# Sheet1.net
KiCad netlist of a schematic drawn in Altium Designer
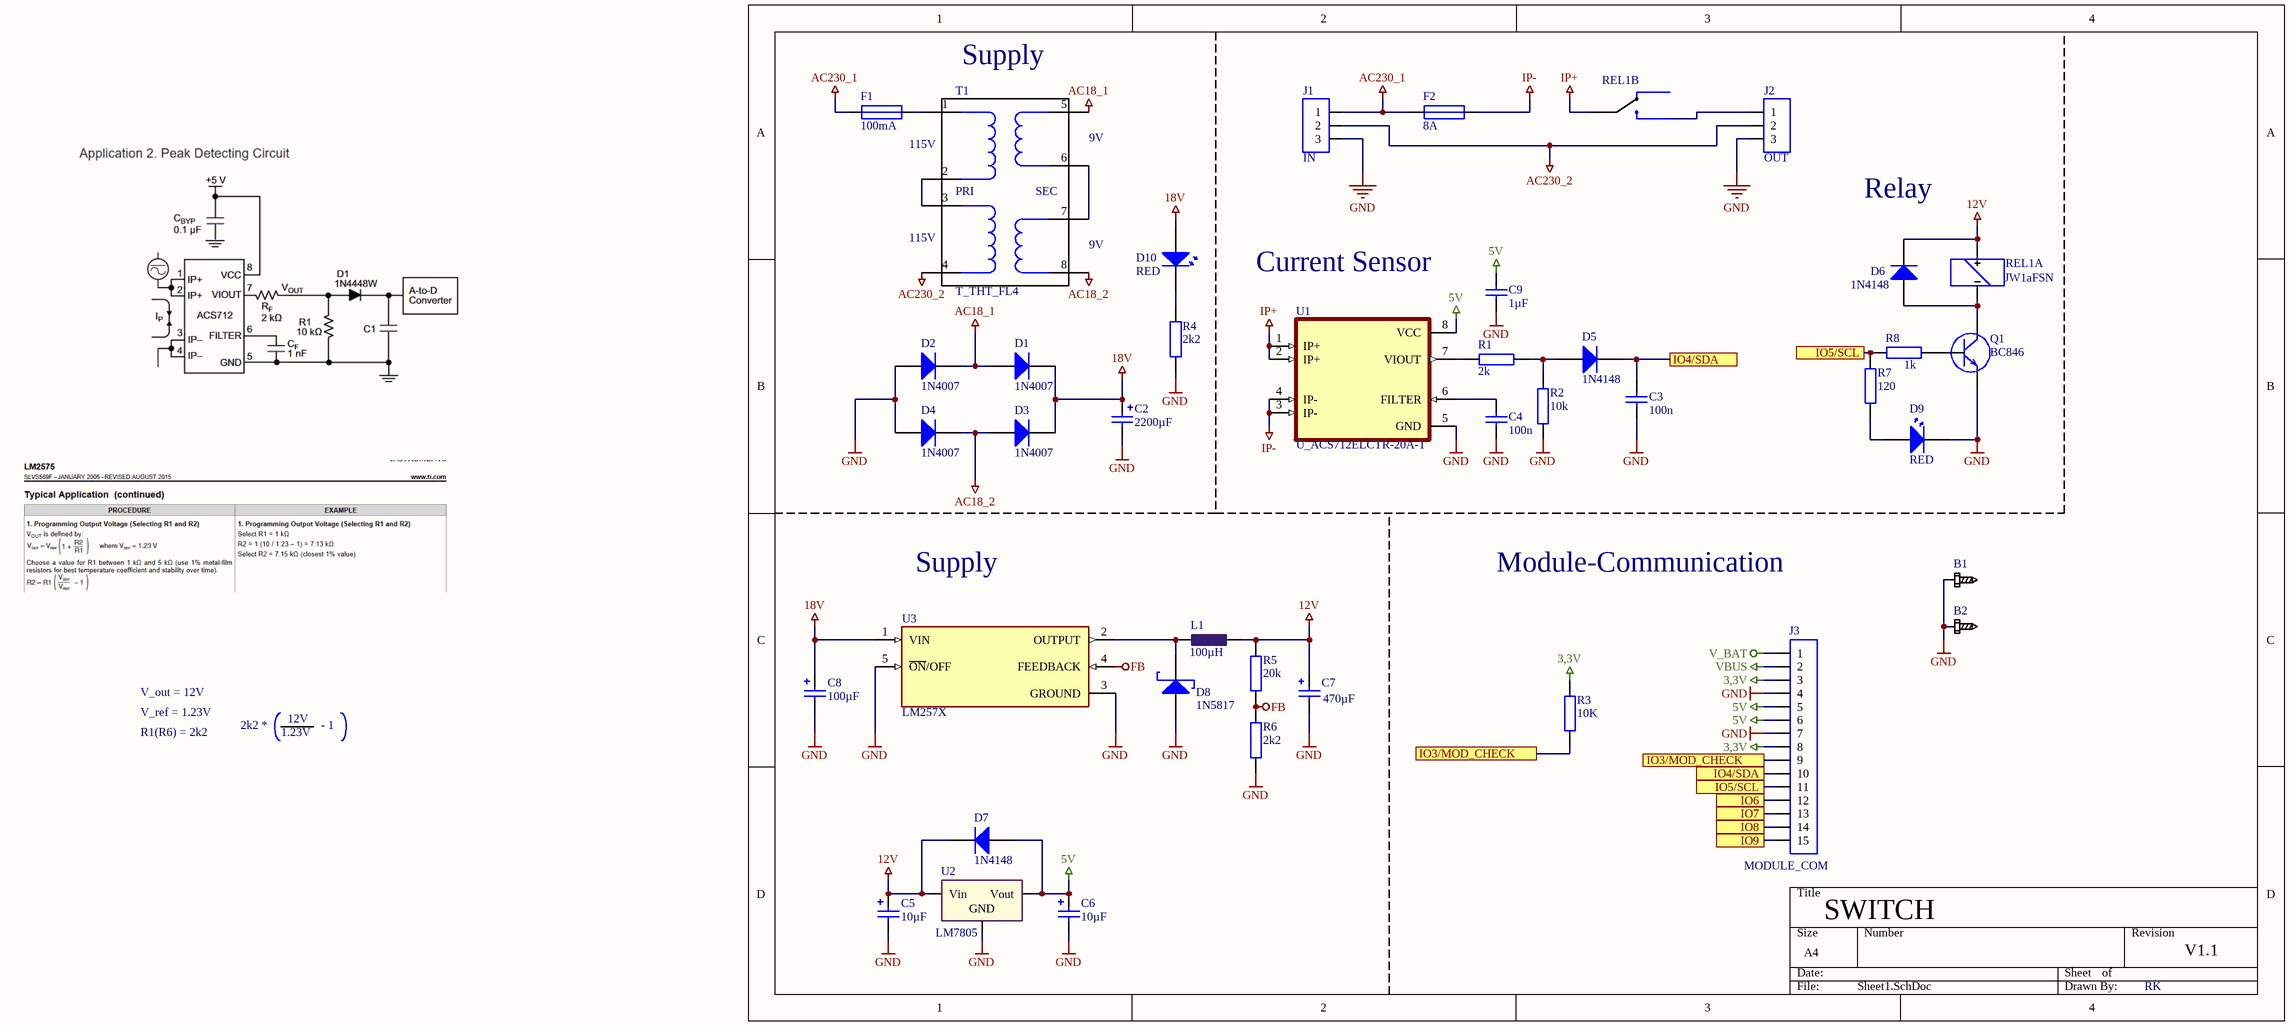
[diagram p0: Sheet1.SchDoc]

(export (version "E")
  (design (tool "Eeschema 10.0.6"))
  (components
    (comp (ref "B1")
      (value "Schraube")
      (footprint "B_Schraube-M3 PAD")
      (description "Schraubenloch für M3 Schrauben")
      (libsource (lib "SCHLIB-PCSB_5.1.3") (part "B_Schraube"))
    )
    (comp (ref "B2")
      (value "Schraube")
      (footprint "B_Schraube-M3 PAD")
      (description "Schraubenloch für M3 Schrauben")
      (libsource (lib "SCHLIB-PCSB_5.1.3") (part "B_Schraube"))
    )
    (comp (ref "C2")
      (value "2200µF")
      (footprint "C_THT_RB-.3/.6")
      (description "THT Elektrolytkondensator")
      (libsource (lib "SCHLIB-PCSB_5.1.3") (part "C_THT_ELK"))
    )
    (comp (ref "C3")
      (value "100n")
      (footprint "C_SMD_0603")
      (description "Kondensator SMD Universal, Keramik, Folie, usw.")
      (libsource (lib "SCHLIB-PCSB_5.1.3") (part "C_SMD_KO"))
    )
    (comp (ref "C4")
      (value "100n")
      (footprint "C_SMD_0603")
      (description "Kondensator SMD Universal, Keramik, Folie, usw.")
      (libsource (lib "SCHLIB-PCSB_5.1.3") (part "C_SMD_KO"))
    )
    (comp (ref "C5")
      (value "10µF")
      (footprint "C_SMD_B-Typ")
      (description "SMD Elektrolytkondensator")
      (libsource (lib "SCHLIB-PCSB_5.1.3") (part "C_SMD_ELK"))
    )
    (comp (ref "C6")
      (value "10µF")
      (footprint "C_SMD_B-Typ")
      (description "SMD Elektrolytkondensator")
      (libsource (lib "SCHLIB-PCSB_5.1.3") (part "C_SMD_ELK"))
    )
    (comp (ref "C7")
      (value "470µF")
      (footprint "C_SMD_B-Typ")
      (description "SMD Elektrolytkondensator")
      (libsource (lib "SCHLIB-PCSB_5.1.3") (part "C_SMD_ELK"))
    )
    (comp (ref "C8")
      (value "100µF")
      (footprint "C_SMD_B-Typ")
      (description "SMD Elektrolytkondensator")
      (libsource (lib "SCHLIB-PCSB_5.1.3") (part "C_SMD_ELK"))
    )
    (comp (ref "C9")
      (value "1µF")
      (footprint "C_SMD_0805")
      (description "Kondensator SMD Universal, Keramik, Folie, usw.")
      (libsource (lib "SCHLIB-PCSB_5.1.3") (part "C_SMD_KO"))
    )
    (comp (ref "D1")
      (value "1N4007")
      (footprint "D_THT_0.4")
      (description "Diode THT Silizium")
      (libsource (lib "SCHLIB-PCSB_5.1.3") (part "D_THT_Silizium"))
    )
    (comp (ref "D2")
      (value "1N4007")
      (footprint "D_THT_0.4")
      (description "Diode THT Silizium")
      (libsource (lib "SCHLIB-PCSB_5.1.3") (part "D_THT_Silizium"))
    )
    (comp (ref "D3")
      (value "1N4007")
      (footprint "D_THT_0.4")
      (description "Diode THT Silizium")
      (libsource (lib "SCHLIB-PCSB_5.1.3") (part "D_THT_Silizium"))
    )
    (comp (ref "D4")
      (value "1N4007")
      (footprint "D_THT_0.4")
      (description "Diode THT Silizium")
      (libsource (lib "SCHLIB-PCSB_5.1.3") (part "D_THT_Silizium"))
    )
    (comp (ref "D5")
      (value "1N4148")
      (footprint "SOD-80-2")
      (description "Diode SMD Silizium")
      (libsource (lib "SCHLIB-PCSB_5.1.3") (part "D_SMD_Silizium"))
    )
    (comp (ref "D6")
      (value "1N4148")
      (footprint "SOD-80-2")
      (description "Diode SMD Silizium")
      (libsource (lib "SCHLIB-PCSB_5.1.3") (part "D_SMD_Silizium"))
    )
    (comp (ref "D7")
      (value "1N4148")
      (footprint "SOD-80-2")
      (description "Diode SMD Silizium")
      (libsource (lib "SCHLIB-PCSB_5.1.3") (part "D_SMD_Silizium"))
    )
    (comp (ref "D8")
      (value "1N5817")
      (footprint "D_THT_0.6")
      (description "Diode THT Schottky")
      (libsource (lib "SCHLIB-PCSB_5.1.3") (part "D_THT_Schottky"))
    )
    (comp (ref "D9")
      (value "RED")
      (footprint "D_THT_LED-3")
      (description "Diode THT LED")
      (libsource (lib "SCHLIB-PCSB_5.1.3") (part "D_THT_LED"))
    )
    (comp (ref "D10")
      (value "RED")
      (footprint "D_THT_LED-3")
      (description "Diode THT LED")
      (libsource (lib "SCHLIB-PCSB_5.1.3") (part "D_THT_LED"))
    )
    (comp (ref "F1")
      (value "100mA")
      (footprint "F_THT_Fuse2pol")
      (description "Sicherung")
      (libsource (lib "SCHLIB-PCSB_5.1.3") (part "F_THT_Fuse"))
    )
    (comp (ref "F2")
      (value "8A")
      (footprint "F_THT_Fuse2pol")
      (description "Sicherung")
      (libsource (lib "SCHLIB-PCSB_5.1.3") (part "F_THT_Fuse"))
    )
    (comp (ref "J1")
      (value "IN")
      (footprint "J_THT_Printklemme 3x")
      (description "Stecker")
      (libsource (lib "SCHLIB-PCSB_5.1.3") (part "J_THT_CON3"))
    )
    (comp (ref "J2")
      (value "OUT")
      (footprint "J_THT_Printklemme 3x")
      (description "Stecker")
      (libsource (lib "") (part "J_THT_CON3_1"))
    )
    (comp (ref "J3")
      (value "MODULE_COM")
      (footprint "SIP-15_Node_V2")
      (description "Stecker")
      (libsource (lib "SCHLIB-PCSB_5.1.3") (part "J_THT_NODE_V2"))
    )
    (comp (ref "L1")
      (value "100µH")
      (footprint "L_SMD_NPIS42LS")
      (description "Spule SMD")
      (libsource (lib "SCHLIB-PCSB_5.1.3") (part "L_SMD_Spule"))
    )
    (comp (ref "Q1")
      (value "BC846")
      (footprint "SOT-23-3_BC846")
      (description "NPN Transistor")
      (libsource (lib "SCHLIB-PCSB_5.1.3") (part "Q_SMD_NPN"))
    )
    (comp (ref "R1")
      (value "2k")
      (footprint "R_SMD_0805")
      (description "Widerstand SMD")
      (libsource (lib "SCHLIB-PCSB_5.1.3") (part "R_SMD_Widerstand"))
    )
    (comp (ref "R2")
      (value "10k")
      (footprint "R_SMD_0805")
      (description "Widerstand SMD")
      (libsource (lib "SCHLIB-PCSB_5.1.3") (part "R_SMD_Widerstand"))
    )
    (comp (ref "R3")
      (value "10K")
      (footprint "R_SMD_0805")
      (description "Widerstand SMD")
      (libsource (lib "SCHLIB-PCSB_5.1.3") (part "R_SMD_Widerstand"))
    )
    (comp (ref "R4")
      (value "2k2")
      (footprint "R_SMD_0805")
      (description "Widerstand SMD")
      (libsource (lib "SCHLIB-PCSB_5.1.3") (part "R_SMD_Widerstand"))
    )
    (comp (ref "R5")
      (value "20k")
      (footprint "R_SMD_0805")
      (description "Widerstand SMD")
      (libsource (lib "SCHLIB-PCSB_5.1.3") (part "R_SMD_Widerstand"))
    )
    (comp (ref "R6")
      (value "2k2")
      (footprint "R_SMD_0805")
      (description "Widerstand SMD")
      (libsource (lib "SCHLIB-PCSB_5.1.3") (part "R_SMD_Widerstand"))
    )
    (comp (ref "R7")
      (value "120")
      (footprint "R_SMD_0805")
      (description "Widerstand SMD")
      (libsource (lib "SCHLIB-PCSB_5.1.3") (part "R_SMD_Widerstand"))
    )
    (comp (ref "R8")
      (value "1k")
      (footprint "R_SMD_0805")
      (description "Widerstand SMD")
      (libsource (lib "SCHLIB-PCSB_5.1.3") (part "R_SMD_Widerstand"))
    )
    (comp (ref "REL1")
      (value "#Wert")
      (footprint "Rel_THT_1x 2")
      (description "Relais 1 Öffner, 1 Schließer")
      (libsource (lib "SCHLIB-PCSB_5.1.3") (part "Rel_THT_1x2"))
    )
    (comp (ref "T1")
      (value "T_THT_FL4")
      (footprint "FL_4_Trafo")
      (description "Flachtrafo von Block 4VA\r\n2x Primär\r\n2x Sekundär")
      (libsource (lib "SCHLIB-PCSB_5.1.3") (part "T_THT_FL4"))
    )
    (comp (ref "U1")
      (value "U_ACS712ELCTR-20A-T")
      (footprint "SO-8")
      (description "Current Sensor 20A 1 Channel Hall Effect, Open Loop Bidirectional 8-SOIC (0.154, 3.90mm Width)")
      (fields (field (name "MF") "Allegro") (field (name "MP") "ACS712ELCTR-20A-T"))
      (libsource (lib "SCHLIB-PCSB_5.1.3") (part "U_ACS712ELCTR-20A-T"))
    )
    (comp (ref "U2")
      (value "LM7805")
      (footprint "TO-220-3H")
      (description "Linearwandler")
      (libsource (lib "SCHLIB-PCSB_5.1.3") (part "U_THT_78xx"))
    )
    (comp (ref "U3")
      (value "LM257X")
      (footprint "TO220-5V")
      (description "Spanungswandler Step Up/Down")
      (libsource (lib "SCHLIB-PCSB_5.1.3") (part "U_THT_LM25xx"))
    )
  )
  (nets
    (net (code "1") (name "/IO3{slash}MOD_CHECK") (class "Default")
      (node (ref "J3") (pin "9") (pinfunction "9_9") (pintype "passive"))
      (node (ref "R3") (pin "1") (pintype "passive"))
    )
    (net (code "2") (name "/IO4{slash}SDA") (class "Default")
      (node (ref "C3") (pin "1") (pintype "passive"))
      (node (ref "D5") (pin "2") (pinfunction "K_2") (pintype "passive"))
      (node (ref "J3") (pin "10") (pinfunction "10_10") (pintype "passive"))
    )
    (net (code "3") (name "/IO5{slash}SCL") (class "Default")
      (node (ref "J3") (pin "11") (pinfunction "11_11") (pintype "passive"))
      (node (ref "R7") (pin "1") (pintype "passive"))
      (node (ref "R8") (pin "1") (pintype "passive"))
    )
    (net (code "4") (name "/IO6") (class "Default")
      (node (ref "J3") (pin "12") (pinfunction "12_12") (pintype "passive"))
    )
    (net (code "5") (name "/IO7") (class "Default")
      (node (ref "J3") (pin "13") (pinfunction "13_13") (pintype "passive"))
    )
    (net (code "6") (name "/IO8") (class "Default")
      (node (ref "J3") (pin "14") (pinfunction "14_14") (pintype "passive"))
    )
    (net (code "7") (name "/IO9") (class "Default")
      (node (ref "J3") (pin "15") (pinfunction "15_15") (pintype "passive"))
    )
    (net (code "8") (name "3,3V") (class "Default")
      (node (ref "J3") (pin "3") (pinfunction "3_3") (pintype "passive"))
      (node (ref "J3") (pin "8") (pinfunction "8_8") (pintype "passive"))
      (node (ref "R3") (pin "2") (pintype "passive"))
    )
    (net (code "9") (name "5V") (class "Default")
      (node (ref "C6") (pin "1") (pinfunction "1_1") (pintype "passive"))
      (node (ref "C9") (pin "1") (pintype "passive"))
      (node (ref "D7") (pin "1") (pinfunction "A_1") (pintype "passive"))
      (node (ref "J3") (pin "5") (pinfunction "5_5") (pintype "passive"))
      (node (ref "J3") (pin "6") (pinfunction "6_6") (pintype "passive"))
      (node (ref "U1") (pin "8") (pinfunction "VCC_8") (pintype "power_in"))
      (node (ref "U2") (pin "2") (pinfunction "Vout_2") (pintype "passive"))
    )
    (net (code "10") (name "12V") (class "Default")
      (node (ref "C5") (pin "1") (pinfunction "1_1") (pintype "passive"))
      (node (ref "C7") (pin "1") (pinfunction "1_1") (pintype "passive"))
      (node (ref "D6") (pin "2") (pinfunction "K_2") (pintype "passive"))
      (node (ref "D7") (pin "2") (pinfunction "K_2") (pintype "passive"))
      (node (ref "L1") (pin "1") (pintype "passive"))
      (node (ref "R5") (pin "1") (pintype "passive"))
      (node (ref "REL1") (pin "1") (pinfunction "+_1") (pintype "passive"))
      (node (ref "U2") (pin "1") (pinfunction "Vin_1") (pintype "passive"))
    )
    (net (code "11") (name "18V") (class "Default")
      (node (ref "C2") (pin "1") (pinfunction "1_1") (pintype "passive"))
      (node (ref "C8") (pin "1") (pinfunction "1_1") (pintype "passive"))
      (node (ref "D1") (pin "2") (pinfunction "K_2") (pintype "passive"))
      (node (ref "D10") (pin "1") (pinfunction "A_1") (pintype "passive"))
      (node (ref "D3") (pin "2") (pinfunction "K_2") (pintype "passive"))
      (node (ref "U3") (pin "1") (pinfunction "VIN_1") (pintype "input"))
    )
    (net (code "12") (name "AC18_1") (class "Default")
      (node (ref "D1") (pin "1") (pinfunction "A_1") (pintype "passive"))
      (node (ref "D2") (pin "2") (pinfunction "K_2") (pintype "passive"))
      (node (ref "T1") (pin "5") (pinfunction "5_5") (pintype "passive"))
    )
    (net (code "13") (name "AC18_2") (class "Default")
      (node (ref "D3") (pin "1") (pinfunction "A_1") (pintype "passive"))
      (node (ref "D4") (pin "2") (pinfunction "K_2") (pintype "passive"))
      (node (ref "T1") (pin "8") (pinfunction "8_8") (pintype "passive"))
    )
    (net (code "14") (name "AC230_1") (class "Default")
      (node (ref "F1") (pin "1") (pintype "passive"))
      (node (ref "F2") (pin "1") (pintype "passive"))
      (node (ref "J1") (pin "1") (pinfunction "1_1") (pintype "passive"))
    )
    (net (code "15") (name "AC230_2") (class "Default")
      (node (ref "J1") (pin "2") (pinfunction "2_2") (pintype "passive"))
      (node (ref "J2") (pin "2") (pinfunction "2_2") (pintype "passive"))
      (node (ref "T1") (pin "4") (pinfunction "4_4") (pintype "passive"))
    )
    (net (code "16") (name "FB") (class "Default")
      (node (ref "R5") (pin "2") (pintype "passive"))
      (node (ref "R6") (pin "1") (pintype "passive"))
      (node (ref "U3") (pin "4") (pinfunction "FEEDBACK_4") (pintype "input"))
    )
    (net (code "17") (name "GND") (class "Default")
      (node (ref "B1") (pin "1") (pinfunction "PAD_1") (pintype "passive"))
      (node (ref "B2") (pin "1") (pinfunction "PAD_1") (pintype "passive"))
      (node (ref "C2") (pin "2") (pinfunction "2_2") (pintype "passive"))
      (node (ref "C3") (pin "2") (pintype "passive"))
      (node (ref "C4") (pin "2") (pintype "passive"))
      (node (ref "C5") (pin "2") (pinfunction "2_2") (pintype "passive"))
      (node (ref "C6") (pin "2") (pinfunction "2_2") (pintype "passive"))
      (node (ref "C7") (pin "2") (pinfunction "2_2") (pintype "passive"))
      (node (ref "C8") (pin "2") (pinfunction "2_2") (pintype "passive"))
      (node (ref "C9") (pin "2") (pintype "passive"))
      (node (ref "D2") (pin "1") (pinfunction "A_1") (pintype "passive"))
      (node (ref "D4") (pin "1") (pinfunction "A_1") (pintype "passive"))
      (node (ref "D8") (pin "1") (pinfunction "A_1") (pintype "passive"))
      (node (ref "D9") (pin "2") (pinfunction "K_2") (pintype "passive"))
      (node (ref "J1") (pin "3") (pinfunction "3_3") (pintype "passive"))
      (node (ref "J2") (pin "3") (pinfunction "3_3") (pintype "passive"))
      (node (ref "J3") (pin "4") (pinfunction "4_4") (pintype "passive"))
      (node (ref "J3") (pin "7") (pinfunction "7_7") (pintype "passive"))
      (node (ref "Q1") (pin "E") (pinfunction "E_E") (pintype "passive"))
      (node (ref "R2") (pin "2") (pintype "passive"))
      (node (ref "R4") (pin "2") (pintype "passive"))
      (node (ref "R6") (pin "2") (pintype "passive"))
      (node (ref "U1") (pin "5") (pinfunction "GND_5") (pintype "power_in"))
      (node (ref "U2") (pin "3") (pinfunction "GND_3") (pintype "passive"))
      (node (ref "U3") (pin "3") (pinfunction "GROUND_3") (pintype "power_in"))
      (node (ref "U3") (pin "5") (pinfunction "~{ON}/OFF_5") (pintype "input"))
    )
    (net (code "18") (name "IP+") (class "Default")
      (node (ref "REL1") (pin "3") (pinfunction "3_3") (pintype "passive"))
      (node (ref "U1") (pin "1") (pinfunction "IP+_1") (pintype "input"))
      (node (ref "U1") (pin "2") (pinfunction "IP+_2") (pintype "input"))
    )
    (net (code "19") (name "IP-") (class "Default")
      (node (ref "F2") (pin "2") (pinfunction "2_2") (pintype "passive"))
      (node (ref "U1") (pin "3") (pinfunction "IP-_3") (pintype "input"))
      (node (ref "U1") (pin "4") (pinfunction "IP-_4") (pintype "input"))
    )
    (net (code "20") (name "Net-(D5-A)") (class "Default")
      (node (ref "D5") (pin "1") (pinfunction "A_1") (pintype "passive"))
      (node (ref "R1") (pin "1") (pintype "passive"))
      (node (ref "R2") (pin "1") (pintype "passive"))
    )
    (net (code "21") (name "Net-(D6-A)") (class "Default")
      (node (ref "D6") (pin "1") (pinfunction "A_1") (pintype "passive"))
      (node (ref "Q1") (pin "C") (pinfunction "C_C") (pintype "passive"))
      (node (ref "REL1") (pin "2") (pinfunction "2_2") (pintype "passive"))
    )
    (net (code "22") (name "Net-(D8-K)") (class "Default")
      (node (ref "D8") (pin "2") (pinfunction "K_2") (pintype "passive"))
      (node (ref "L1") (pin "2") (pintype "passive"))
      (node (ref "U3") (pin "2") (pinfunction "OUTPUT_2") (pintype "output"))
    )
    (net (code "23") (name "Net-(D9-A)") (class "Default")
      (node (ref "D9") (pin "1") (pinfunction "A_1") (pintype "passive"))
      (node (ref "R7") (pin "2") (pintype "passive"))
    )
    (net (code "24") (name "Net-(D10-K)") (class "Default")
      (node (ref "D10") (pin "2") (pinfunction "K_2") (pintype "passive"))
      (node (ref "R4") (pin "1") (pintype "passive"))
    )
    (net (code "25") (name "Net-(F1-Pad2)") (class "Default")
      (node (ref "F1") (pin "2") (pinfunction "2_2") (pintype "passive"))
      (node (ref "T1") (pin "1") (pinfunction "1_1") (pintype "passive"))
    )
    (net (code "26") (name "Net-(Q1-PadB)") (class "Default")
      (node (ref "Q1") (pin "B") (pinfunction "B_B") (pintype "passive"))
      (node (ref "R8") (pin "2") (pintype "passive"))
    )
    (net (code "27") (name "Net-(REL1B-NO)") (class "Default")
      (node (ref "J2") (pin "1") (pinfunction "1_1") (pintype "passive"))
      (node (ref "REL1") (pin "4") (pinfunction "NO_4") (pintype "passive"))
    )
    (net (code "28") (name "Net-(T1-Pad2)") (class "Default")
      (node (ref "T1") (pin "2") (pinfunction "2_2") (pintype "passive"))
      (node (ref "T1") (pin "3") (pinfunction "3_3") (pintype "passive"))
    )
    (net (code "29") (name "Net-(T1-Pad6)") (class "Default")
      (node (ref "T1") (pin "6") (pinfunction "6_6") (pintype "passive"))
      (node (ref "T1") (pin "7") (pinfunction "7_7") (pintype "passive"))
    )
    (net (code "30") (name "Net-(U1-FILTER)") (class "Default")
      (node (ref "C4") (pin "1") (pintype "passive"))
      (node (ref "U1") (pin "6") (pinfunction "FILTER_6") (pintype "input"))
    )
    (net (code "31") (name "Net-(U1-VIOUT)") (class "Default")
      (node (ref "R1") (pin "2") (pintype "passive"))
      (node (ref "U1") (pin "7") (pinfunction "VIOUT_7") (pintype "output"))
    )
    (net (code "32") (name "VBUS") (class "Default")
      (node (ref "J3") (pin "2") (pinfunction "2_2") (pintype "passive"))
    )
    (net (code "33") (name "V_BAT") (class "Default")
      (node (ref "J3") (pin "1") (pinfunction "1_1") (pintype "passive"))
    )
    (net (code "34") (name "unconnected-(REL1-Pad5)") (class "Default")
      (node (ref "REL1") (pin "5") (pinfunction "5_5") (pintype "passive"))
    )
  )
)
